# Ponte_Raddrizzatore.net
KiCad netlist of a schematic drawn in EAGLE
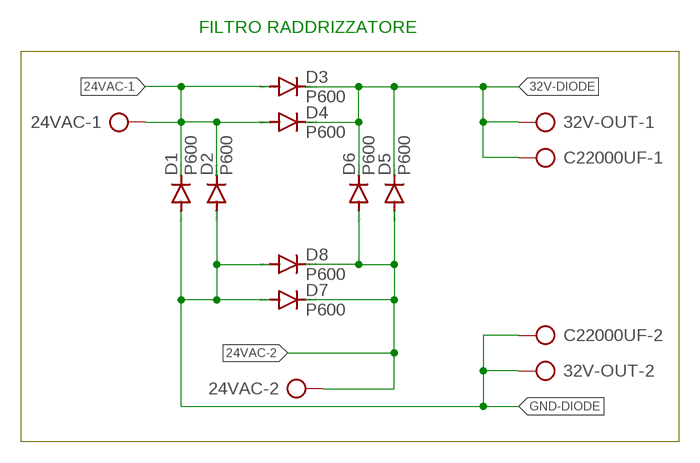
[diagram p0: schematic, sheet 1]

(export (version "E")
  (design (tool "Eeschema 10.0.6"))
  (components
    (comp (ref "24VAC")
      (value "SMKDSP_1,5/2")
      (footprint "eagle-import:SMKDSP_1,5_2")
      (fields (field (name "MF") "FARNELL") (field (name "MPN") "1733570"))
      (libsource (lib "eagle-import") (part "SMKDSP_1,5/2"))
    )
    (comp (ref "32V-OUT")
      (value "SMKDSP_1,5/2")
      (footprint "eagle-import:SMKDSP_1,5_2")
      (fields (field (name "MF") "FARNELL") (field (name "MPN") "1733570"))
      (libsource (lib "eagle-import") (part "SMKDSP_1,5/2"))
    )
    (comp (ref "C22000UF")
      (value "SMKDSP_1,5/2")
      (footprint "eagle-import:SMKDSP_1,5_2")
      (fields (field (name "MF") "FARNELL") (field (name "MPN") "1733570"))
      (libsource (lib "eagle-import") (part "SMKDSP_1,5/2"))
    )
    (comp (ref "D1")
      (value "P600")
      (footprint "eagle-import:P6-15")
      (libsource (lib "eagle-import") (part "P600"))
    )
    (comp (ref "D2")
      (value "P600")
      (footprint "eagle-import:P6-15")
      (libsource (lib "eagle-import") (part "P600"))
    )
    (comp (ref "D3")
      (value "P600")
      (footprint "eagle-import:P6-15")
      (libsource (lib "eagle-import") (part "P600"))
    )
    (comp (ref "D4")
      (value "P600")
      (footprint "eagle-import:P6-15")
      (libsource (lib "eagle-import") (part "P600"))
    )
    (comp (ref "D5")
      (value "P600")
      (footprint "eagle-import:P6-15")
      (libsource (lib "eagle-import") (part "P600"))
    )
    (comp (ref "D6")
      (value "P600")
      (footprint "eagle-import:P6-15")
      (libsource (lib "eagle-import") (part "P600"))
    )
    (comp (ref "D7")
      (value "P600")
      (footprint "eagle-import:P6-15")
      (libsource (lib "eagle-import") (part "P600"))
    )
    (comp (ref "D8")
      (value "P600")
      (footprint "eagle-import:P6-15")
      (libsource (lib "eagle-import") (part "P600"))
    )
  )
  (nets
    (net (code "1") (name "24VAC-1") (class "Default")
      (node (ref "24VAC") (pin "1") (pinfunction "KL_1") (pintype "passive"))
      (node (ref "D1") (pin "C") (pinfunction "C_C") (pintype "passive"))
      (node (ref "D2") (pin "C") (pinfunction "C_C") (pintype "passive"))
      (node (ref "D3") (pin "A") (pinfunction "A_A") (pintype "passive"))
      (node (ref "D4") (pin "A") (pinfunction "A_A") (pintype "passive"))
    )
    (net (code "2") (name "24VAC-2") (class "Default")
      (node (ref "24VAC") (pin "2") (pinfunction "KL_2") (pintype "passive"))
      (node (ref "D5") (pin "A") (pinfunction "A_A") (pintype "passive"))
      (node (ref "D6") (pin "A") (pinfunction "A_A") (pintype "passive"))
      (node (ref "D7") (pin "C") (pinfunction "C_C") (pintype "passive"))
      (node (ref "D8") (pin "C") (pinfunction "C_C") (pintype "passive"))
    )
    (net (code "3") (name "32V-DIODE") (class "Default")
      (node (ref "32V-OUT") (pin "1") (pinfunction "KL_1") (pintype "passive"))
      (node (ref "C22000UF") (pin "1") (pinfunction "KL_1") (pintype "passive"))
      (node (ref "D3") (pin "C") (pinfunction "C_C") (pintype "passive"))
      (node (ref "D4") (pin "C") (pinfunction "C_C") (pintype "passive"))
      (node (ref "D5") (pin "C") (pinfunction "C_C") (pintype "passive"))
      (node (ref "D6") (pin "C") (pinfunction "C_C") (pintype "passive"))
    )
    (net (code "4") (name "GND-DIODE") (class "Default")
      (node (ref "32V-OUT") (pin "2") (pinfunction "KL_2") (pintype "passive"))
      (node (ref "C22000UF") (pin "2") (pinfunction "KL_2") (pintype "passive"))
      (node (ref "D1") (pin "A") (pinfunction "A_A") (pintype "passive"))
      (node (ref "D2") (pin "A") (pinfunction "A_A") (pintype "passive"))
      (node (ref "D7") (pin "A") (pinfunction "A_A") (pintype "passive"))
      (node (ref "D8") (pin "A") (pinfunction "A_A") (pintype "passive"))
    )
  )
)
